# POWER_PCie.net
KiCad netlist of a schematic drawn in Altium Designer
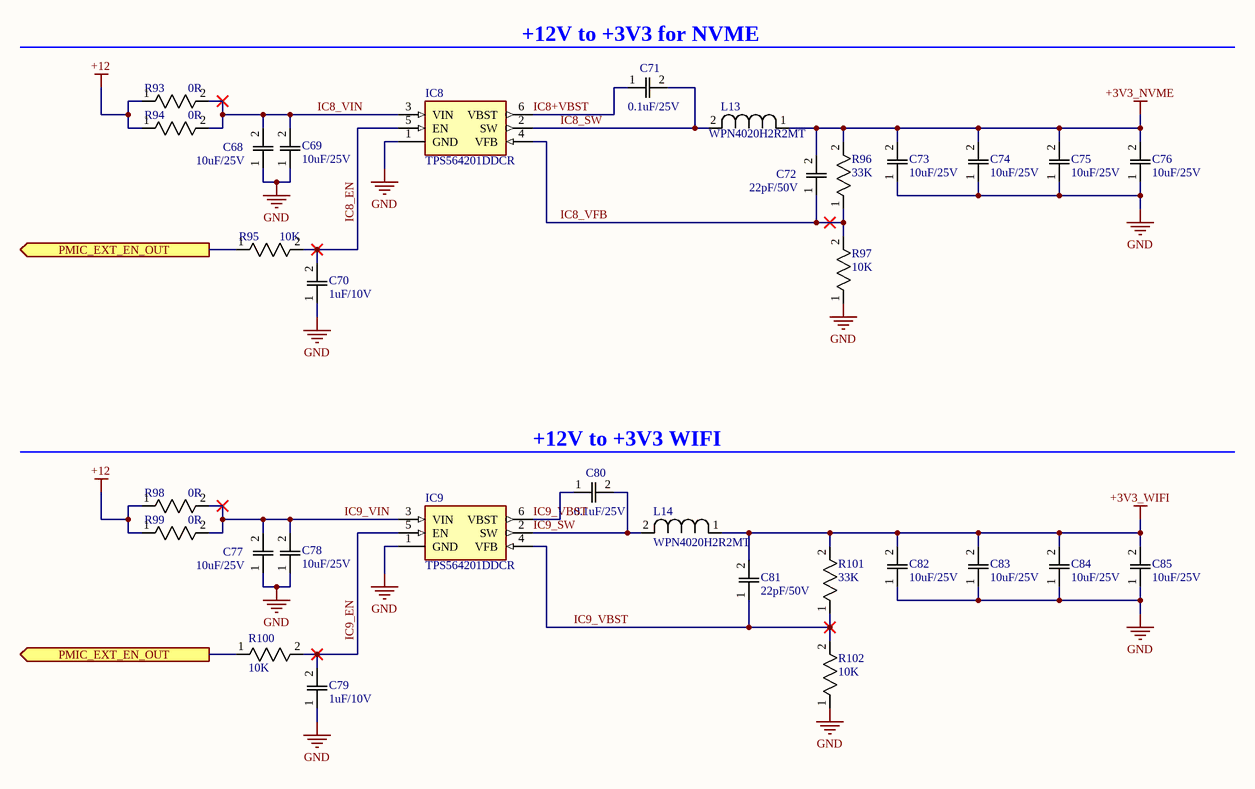
[diagram p0: POWER_PCie.SchDoc]

(export (version "E")
  (design (tool "Eeschema 10.0.6"))
  (components
    (comp (ref "C68")
      (value "10uF/25V")
      (footprint "C0805")
      (description "10uF / 25 VDC, +85degC, X5R Dielec, +/-10% ¦ KEMET C0805C106K3PACTU 0805")
      (fields
        (field (name "MANUFACTURER") "KEMET")
        (field (name "MANUFACTURER PART NUMBER") "C0805C106K3PACTU")
      )
      (libsource (lib "DARKYDEN") (part "C0805C106K3PACTU"))
    )
    (comp (ref "C69")
      (value "10uF/25V")
      (footprint "C0805")
      (description "10uF / 25 VDC, +85degC, X5R Dielec, +/-10% ¦ KEMET C0805C106K3PACTU 0805")
      (fields
        (field (name "MANUFACTURER") "KEMET")
        (field (name "MANUFACTURER PART NUMBER") "C0805C106K3PACTU")
      )
      (libsource (lib "DARKYDEN") (part "C0805C106K3PACTU"))
    )
    (comp (ref "C70")
      (value "1uF/10V")
      (footprint "C0805")
      (description "Multilayer Ceramic Capacitors MLCC - SMD/SMT 10V 1uF X7R 0805 10%")
      (fields
        (field (name "MANUFACTURER") "KEMET")
        (field (name "MANUFACTURER PART NUMBER") "C0805C105K8RACTU")
      )
      (libsource (lib "DARKYDEN") (part "C0805C105K8RACTU"))
    )
    (comp (ref "C71")
      (value "0.1uF/25V")
      (footprint "c0805")
      (description "0.1uF 25V X7R 10% SMD 0805 125C Plastic T/R")
      (fields
        (field (name "MANUFACTURER") "KEMET")
        (field (name "MANUFACTURER PART NUMBER") "C0805C104K3RACTU")
      )
      (libsource (lib "DARKYDEN") (part "C0805C104K3RACTU"))
    )
    (comp (ref "C72")
      (value "22pF/50V")
      (footprint "C0805")
      (description "Cap Ceramic 22pF 50V X7R 5% Pad SMD 0805 125°C T/R")
      (fields
        (field (name "MANUFACTURER") "KEMET")
        (field (name "MANUFACTURER PART NUMBER") "C0805C220J5RACTU")
      )
      (libsource (lib "DARKYDEN") (part "C0805C220J5RACTU"))
    )
    (comp (ref "C73")
      (value "10uF/25V")
      (footprint "C0805")
      (description "10uF / 25 VDC, +85degC, X5R Dielec, +/-10% ¦ KEMET C0805C106K3PACTU 0805")
      (fields
        (field (name "MANUFACTURER") "KEMET")
        (field (name "MANUFACTURER PART NUMBER") "C0805C106K3PACTU")
      )
      (libsource (lib "DARKYDEN") (part "C0805C106K3PACTU"))
    )
    (comp (ref "C74")
      (value "10uF/25V")
      (footprint "C0805")
      (description "10uF / 25 VDC, +85degC, X5R Dielec, +/-10% ¦ KEMET C0805C106K3PACTU 0805")
      (fields
        (field (name "MANUFACTURER") "KEMET")
        (field (name "MANUFACTURER PART NUMBER") "C0805C106K3PACTU")
      )
      (libsource (lib "DARKYDEN") (part "C0805C106K3PACTU"))
    )
    (comp (ref "C75")
      (value "10uF/25V")
      (footprint "C0805")
      (description "10uF / 25 VDC, +85degC, X5R Dielec, +/-10% ¦ KEMET C0805C106K3PACTU 0805")
      (fields
        (field (name "MANUFACTURER") "KEMET")
        (field (name "MANUFACTURER PART NUMBER") "C0805C106K3PACTU")
      )
      (libsource (lib "DARKYDEN") (part "C0805C106K3PACTU"))
    )
    (comp (ref "C76")
      (value "10uF/25V")
      (footprint "C0805")
      (description "10uF / 25 VDC, +85degC, X5R Dielec, +/-10% ¦ KEMET C0805C106K3PACTU 0805")
      (fields
        (field (name "MANUFACTURER") "KEMET")
        (field (name "MANUFACTURER PART NUMBER") "C0805C106K3PACTU")
      )
      (libsource (lib "DARKYDEN") (part "C0805C106K3PACTU"))
    )
    (comp (ref "C77")
      (value "10uF/25V")
      (footprint "C0805")
      (description "10uF / 25 VDC, +85degC, X5R Dielec, +/-10% ¦ KEMET C0805C106K3PACTU 0805")
      (fields
        (field (name "MANUFACTURER") "KEMET")
        (field (name "MANUFACTURER PART NUMBER") "C0805C106K3PACTU")
      )
      (libsource (lib "DARKYDEN") (part "C0805C106K3PACTU"))
    )
    (comp (ref "C78")
      (value "10uF/25V")
      (footprint "C0805")
      (description "10uF / 25 VDC, +85degC, X5R Dielec, +/-10% ¦ KEMET C0805C106K3PACTU 0805")
      (fields
        (field (name "MANUFACTURER") "KEMET")
        (field (name "MANUFACTURER PART NUMBER") "C0805C106K3PACTU")
      )
      (libsource (lib "DARKYDEN") (part "C0805C106K3PACTU"))
    )
    (comp (ref "C79")
      (value "1uF/10V")
      (footprint "C0805")
      (description "Multilayer Ceramic Capacitors MLCC - SMD/SMT 10V 1uF X7R 0805 10%")
      (fields
        (field (name "MANUFACTURER") "KEMET")
        (field (name "MANUFACTURER PART NUMBER") "C0805C105K8RACTU")
      )
      (libsource (lib "DARKYDEN") (part "C0805C105K8RACTU"))
    )
    (comp (ref "C80")
      (value "0.1uF/25V")
      (footprint "c0805")
      (description "0.1uF 25V X7R 10% SMD 0805 125C Plastic T/R")
      (fields
        (field (name "MANUFACTURER") "KEMET")
        (field (name "MANUFACTURER PART NUMBER") "C0805C104K3RACTU")
      )
      (libsource (lib "DARKYDEN") (part "C0805C104K3RACTU"))
    )
    (comp (ref "C81")
      (value "22pF/50V")
      (footprint "C0805")
      (description "Cap Ceramic 22pF 50V X7R 5% Pad SMD 0805 125°C T/R")
      (fields
        (field (name "MANUFACTURER") "KEMET")
        (field (name "MANUFACTURER PART NUMBER") "C0805C220J5RACTU")
      )
      (libsource (lib "DARKYDEN") (part "C0805C220J5RACTU"))
    )
    (comp (ref "C82")
      (value "10uF/25V")
      (footprint "C0805")
      (description "10uF / 25 VDC, +85degC, X5R Dielec, +/-10% ¦ KEMET C0805C106K3PACTU 0805")
      (fields
        (field (name "MANUFACTURER") "KEMET")
        (field (name "MANUFACTURER PART NUMBER") "C0805C106K3PACTU")
      )
      (libsource (lib "DARKYDEN") (part "C0805C106K3PACTU"))
    )
    (comp (ref "C83")
      (value "10uF/25V")
      (footprint "C0805")
      (description "10uF / 25 VDC, +85degC, X5R Dielec, +/-10% ¦ KEMET C0805C106K3PACTU 0805")
      (fields
        (field (name "MANUFACTURER") "KEMET")
        (field (name "MANUFACTURER PART NUMBER") "C0805C106K3PACTU")
      )
      (libsource (lib "DARKYDEN") (part "C0805C106K3PACTU"))
    )
    (comp (ref "C84")
      (value "10uF/25V")
      (footprint "C0805")
      (description "10uF / 25 VDC, +85degC, X5R Dielec, +/-10% ¦ KEMET C0805C106K3PACTU 0805")
      (fields
        (field (name "MANUFACTURER") "KEMET")
        (field (name "MANUFACTURER PART NUMBER") "C0805C106K3PACTU")
      )
      (libsource (lib "DARKYDEN") (part "C0805C106K3PACTU"))
    )
    (comp (ref "C85")
      (value "10uF/25V")
      (footprint "C0805")
      (description "10uF / 25 VDC, +85degC, X5R Dielec, +/-10% ¦ KEMET C0805C106K3PACTU 0805")
      (fields
        (field (name "MANUFACTURER") "KEMET")
        (field (name "MANUFACTURER PART NUMBER") "C0805C106K3PACTU")
      )
      (libsource (lib "DARKYDEN") (part "C0805C106K3PACTU"))
    )
    (comp (ref "IC8")
      (value "TPS564201DDCR")
      (footprint "SamacSys:SOT95P280X110-6N")
      (fields
        (field (name "MOUSER PART NUMBER") "595-TPS564201DDCR")
        (field (name "MANUFACTURER") "Texas Instruments")
      )
      (libsource (lib "SamacSys") (part "TPS564201DDCR"))
    )
    (comp (ref "IC9")
      (value "TPS564201DDCR")
      (footprint "SamacSys:SOT95P280X110-6N")
      (fields
        (field (name "MOUSER PART NUMBER") "595-TPS564201DDCR")
        (field (name "MANUFACTURER") "Texas Instruments")
      )
      (libsource (lib "SamacSys") (part "TPS564201DDCR"))
    )
    (comp (ref "L13")
      (value "WPN4020H2R2MT")
      (footprint "WPN4020H2R2MT:IND_WPN4020H_SNL")
      (description "2.2 µH Shielded Drum Core, Wirewound Inductor 4.3 A 48mOhm Max Nonstandard")
      (fields (field (name "MANUFACTURER") "Sunlord"))
      (libsource (lib "DARKYDEN") (part "WPN4020H2R2MT"))
    )
    (comp (ref "L14")
      (value "WPN4020H2R2MT")
      (footprint "WPN4020H2R2MT:IND_WPN4020H_SNL")
      (description "2.2 µH Shielded Drum Core, Wirewound Inductor 4.3 A 48mOhm Max Nonstandard")
      (fields (field (name "MANUFACTURER") "Sunlord"))
      (libsource (lib "DARKYDEN") (part "WPN4020H2R2MT"))
    )
    (comp (ref "R93")
      (value "0R")
      (footprint "SamacSys:RESC1608X55N")
      (description "Zero Ohm Resistor, Jumper, 0603 [1608 Metric], Thick Film, 100 mW, 1 A, Surface Mount")
      (fields
        (field (name "MANUFACTURER_PART_NUMBER") "ERJ-3GEY0R00V")
        (field (name "MOUSER PART NUMBER") "667-ERJ-3GEY0R00V")
      )
      (libsource (lib "DARKYDEN") (part "ERJ-3GEY0R00V"))
    )
    (comp (ref "R94")
      (value "0R")
      (footprint "SamacSys:RESC1608X55N")
      (description "Zero Ohm Resistor, Jumper, 0603 [1608 Metric], Thick Film, 100 mW, 1 A, Surface Mount")
      (fields
        (field (name "MANUFACTURER_PART_NUMBER") "ERJ-3GEY0R00V")
        (field (name "MOUSER PART NUMBER") "667-ERJ-3GEY0R00V")
      )
      (libsource (lib "DARKYDEN") (part "ERJ-3GEY0R00V"))
    )
    (comp (ref "R95")
      (value "10K")
      (footprint "SamacSys:RESC1608X55N")
      (description "10K Ohm 5% Res Thick Film 0603  0.1W(1/10W) ±200ppm/C Pad SMD Automotive T/R")
      (fields
        (field (name "MANUFACTURER_PART_NUMBER") "ERJ-3GEYJ103V")
        (field (name "MOUSER PART NUMBER") "667-ERJ-3GEYJ103V")
      )
      (libsource (lib "DARKYDEN") (part "ERJ-3GEYJ103V"))
    )
    (comp (ref "R96")
      (value "33K")
      (footprint "SamacSys:RESC1608X55N")
      (description "33K Ohm 0603  5% 0.1W(1/10W) +/-200ppm/ßC SMD Automotive T/R")
      (fields
        (field (name "MANUFACTURER_PART_NUMBER") "ERJ-3GEYJ333V")
        (field (name "MOUSER PART NUMBER") "667-ERJ-3GEYJ333V")
      )
      (libsource (lib "DARKYDEN") (part "ERJ-3GEYJ333V"))
    )
    (comp (ref "R97")
      (value "10K")
      (footprint "SamacSys:RESC1608X55N")
      (description "10K Ohm 5% Res Thick Film 0603  0.1W(1/10W) ±200ppm/C Pad SMD Automotive T/R")
      (fields
        (field (name "MANUFACTURER_PART_NUMBER") "ERJ-3GEYJ103V")
        (field (name "MOUSER PART NUMBER") "667-ERJ-3GEYJ103V")
      )
      (libsource (lib "DARKYDEN") (part "ERJ-3GEYJ103V"))
    )
    (comp (ref "R98")
      (value "0R")
      (footprint "SamacSys:RESC1608X55N")
      (description "Zero Ohm Resistor, Jumper, 0603 [1608 Metric], Thick Film, 100 mW, 1 A, Surface Mount")
      (fields
        (field (name "MANUFACTURER_PART_NUMBER") "ERJ-3GEY0R00V")
        (field (name "MOUSER PART NUMBER") "667-ERJ-3GEY0R00V")
      )
      (libsource (lib "DARKYDEN") (part "ERJ-3GEY0R00V"))
    )
    (comp (ref "R99")
      (value "0R")
      (footprint "SamacSys:RESC1608X55N")
      (description "Zero Ohm Resistor, Jumper, 0603 [1608 Metric], Thick Film, 100 mW, 1 A, Surface Mount")
      (fields
        (field (name "MANUFACTURER_PART_NUMBER") "ERJ-3GEY0R00V")
        (field (name "MOUSER PART NUMBER") "667-ERJ-3GEY0R00V")
      )
      (libsource (lib "DARKYDEN") (part "ERJ-3GEY0R00V"))
    )
    (comp (ref "R100")
      (value "10K")
      (footprint "SamacSys:RESC1608X55N")
      (description "10K Ohm 5% Res Thick Film 0603  0.1W(1/10W) ±200ppm/C Pad SMD Automotive T/R")
      (fields
        (field (name "MANUFACTURER_PART_NUMBER") "ERJ-3GEYJ103V")
        (field (name "MOUSER PART NUMBER") "667-ERJ-3GEYJ103V")
      )
      (libsource (lib "DARKYDEN") (part "ERJ-3GEYJ103V"))
    )
    (comp (ref "R101")
      (value "33K")
      (footprint "SamacSys:RESC1608X55N")
      (description "33K Ohm 0603  5% 0.1W(1/10W) +/-200ppm/ßC SMD Automotive T/R")
      (fields
        (field (name "MANUFACTURER_PART_NUMBER") "ERJ-3GEYJ333V")
        (field (name "MOUSER PART NUMBER") "667-ERJ-3GEYJ333V")
      )
      (libsource (lib "DARKYDEN") (part "ERJ-3GEYJ333V"))
    )
    (comp (ref "R102")
      (value "10K")
      (footprint "SamacSys:RESC1608X55N")
      (description "10K Ohm 5% Res Thick Film 0603  0.1W(1/10W) ±200ppm/C Pad SMD Automotive T/R")
      (fields
        (field (name "MANUFACTURER_PART_NUMBER") "ERJ-3GEYJ103V")
        (field (name "MOUSER PART NUMBER") "667-ERJ-3GEYJ103V")
      )
      (libsource (lib "DARKYDEN") (part "ERJ-3GEYJ103V"))
    )
  )
  (nets
    (net (code "1") (name "+3V3_NVME") (class "Default")
      (node (ref "C72") (pin "2") (pinfunction "2_2") (pintype "passive"))
      (node (ref "C73") (pin "2") (pinfunction "2_2") (pintype "passive"))
      (node (ref "C74") (pin "2") (pinfunction "2_2") (pintype "passive"))
      (node (ref "C75") (pin "2") (pinfunction "2_2") (pintype "passive"))
      (node (ref "C76") (pin "2") (pinfunction "2_2") (pintype "passive"))
      (node (ref "L13") (pin "1") (pinfunction "1_1") (pintype "passive"))
      (node (ref "R96") (pin "2") (pinfunction "2_2") (pintype "passive"))
    )
    (net (code "2") (name "+3V3_WIFI") (class "Default")
      (node (ref "C81") (pin "2") (pinfunction "2_2") (pintype "passive"))
      (node (ref "C82") (pin "2") (pinfunction "2_2") (pintype "passive"))
      (node (ref "C83") (pin "2") (pinfunction "2_2") (pintype "passive"))
      (node (ref "C84") (pin "2") (pinfunction "2_2") (pintype "passive"))
      (node (ref "C85") (pin "2") (pinfunction "2_2") (pintype "passive"))
      (node (ref "L14") (pin "1") (pinfunction "1_1") (pintype "passive"))
      (node (ref "R101") (pin "2") (pinfunction "2_2") (pintype "passive"))
    )
    (net (code "3") (name "+12") (class "Default")
      (node (ref "R93") (pin "1") (pinfunction "1_1") (pintype "passive"))
      (node (ref "R94") (pin "1") (pinfunction "1_1") (pintype "passive"))
      (node (ref "R98") (pin "1") (pinfunction "1_1") (pintype "passive"))
      (node (ref "R99") (pin "1") (pinfunction "1_1") (pintype "passive"))
    )
    (net (code "4") (name "/IC8+VBST") (class "Default")
      (node (ref "C71") (pin "1") (pinfunction "1_1") (pintype "passive"))
      (node (ref "IC8") (pin "6") (pinfunction "VBST_6") (pintype "output"))
    )
    (net (code "5") (name "/IC8_EN") (class "Default")
      (node (ref "C70") (pin "2") (pinfunction "2_2") (pintype "passive"))
      (node (ref "IC8") (pin "5") (pinfunction "EN_5") (pintype "input"))
      (node (ref "R95") (pin "2") (pinfunction "2_2") (pintype "passive"))
    )
    (net (code "6") (name "/IC8_SW") (class "Default")
      (node (ref "C71") (pin "2") (pinfunction "2_2") (pintype "passive"))
      (node (ref "IC8") (pin "2") (pinfunction "SW_2") (pintype "output"))
      (node (ref "L13") (pin "2") (pinfunction "2_2") (pintype "passive"))
    )
    (net (code "7") (name "/IC8_VFB") (class "Default")
      (node (ref "C72") (pin "1") (pinfunction "1_1") (pintype "passive"))
      (node (ref "IC8") (pin "4") (pinfunction "VFB_4") (pintype "input"))
      (node (ref "R96") (pin "1") (pinfunction "1_1") (pintype "passive"))
      (node (ref "R97") (pin "2") (pinfunction "2_2") (pintype "passive"))
    )
    (net (code "8") (name "/IC8_VIN") (class "Default")
      (node (ref "C68") (pin "2") (pinfunction "2_2") (pintype "passive"))
      (node (ref "C69") (pin "2") (pinfunction "2_2") (pintype "passive"))
      (node (ref "IC8") (pin "3") (pinfunction "VIN_3") (pintype "input"))
      (node (ref "R93") (pin "2") (pinfunction "2_2") (pintype "passive"))
      (node (ref "R94") (pin "2") (pinfunction "2_2") (pintype "passive"))
    )
    (net (code "9") (name "/IC9_EN") (class "Default")
      (node (ref "C79") (pin "2") (pinfunction "2_2") (pintype "passive"))
      (node (ref "IC9") (pin "5") (pinfunction "EN_5") (pintype "input"))
      (node (ref "R100") (pin "2") (pinfunction "2_2") (pintype "passive"))
    )
    (net (code "10") (name "/IC9_SW") (class "Default")
      (node (ref "C80") (pin "2") (pinfunction "2_2") (pintype "passive"))
      (node (ref "IC9") (pin "2") (pinfunction "SW_2") (pintype "output"))
      (node (ref "L14") (pin "2") (pinfunction "2_2") (pintype "passive"))
    )
    (net (code "11") (name "/IC9_VBST") (class "Default")
      (node (ref "C80") (pin "1") (pinfunction "1_1") (pintype "passive"))
      (node (ref "C81") (pin "1") (pinfunction "1_1") (pintype "passive"))
      (node (ref "IC9") (pin "4") (pinfunction "VFB_4") (pintype "input"))
      (node (ref "IC9") (pin "6") (pinfunction "VBST_6") (pintype "output"))
      (node (ref "R101") (pin "1") (pinfunction "1_1") (pintype "passive"))
      (node (ref "R102") (pin "2") (pinfunction "2_2") (pintype "passive"))
    )
    (net (code "12") (name "/IC9_VIN") (class "Default")
      (node (ref "C77") (pin "2") (pinfunction "2_2") (pintype "passive"))
      (node (ref "C78") (pin "2") (pinfunction "2_2") (pintype "passive"))
      (node (ref "IC9") (pin "3") (pinfunction "VIN_3") (pintype "input"))
      (node (ref "R98") (pin "2") (pinfunction "2_2") (pintype "passive"))
      (node (ref "R99") (pin "2") (pinfunction "2_2") (pintype "passive"))
    )
    (net (code "13") (name "/PMIC_EXT_EN_OUT") (class "Default")
      (node (ref "R100") (pin "1") (pinfunction "1_1") (pintype "passive"))
      (node (ref "R95") (pin "1") (pinfunction "1_1") (pintype "passive"))
    )
    (net (code "14") (name "GND") (class "Default")
      (node (ref "C68") (pin "1") (pinfunction "1_1") (pintype "passive"))
      (node (ref "C69") (pin "1") (pinfunction "1_1") (pintype "passive"))
      (node (ref "C70") (pin "1") (pinfunction "1_1") (pintype "passive"))
      (node (ref "C73") (pin "1") (pinfunction "1_1") (pintype "passive"))
      (node (ref "C74") (pin "1") (pinfunction "1_1") (pintype "passive"))
      (node (ref "C75") (pin "1") (pinfunction "1_1") (pintype "passive"))
      (node (ref "C76") (pin "1") (pinfunction "1_1") (pintype "passive"))
      (node (ref "C77") (pin "1") (pinfunction "1_1") (pintype "passive"))
      (node (ref "C78") (pin "1") (pinfunction "1_1") (pintype "passive"))
      (node (ref "C79") (pin "1") (pinfunction "1_1") (pintype "passive"))
      (node (ref "C82") (pin "1") (pinfunction "1_1") (pintype "passive"))
      (node (ref "C83") (pin "1") (pinfunction "1_1") (pintype "passive"))
      (node (ref "C84") (pin "1") (pinfunction "1_1") (pintype "passive"))
      (node (ref "C85") (pin "1") (pinfunction "1_1") (pintype "passive"))
      (node (ref "IC8") (pin "1") (pinfunction "GND_1") (pintype "passive"))
      (node (ref "IC9") (pin "1") (pinfunction "GND_1") (pintype "passive"))
      (node (ref "R102") (pin "1") (pinfunction "1_1") (pintype "passive"))
      (node (ref "R97") (pin "1") (pinfunction "1_1") (pintype "passive"))
    )
  )
)
